# Tj_Monitor.net
KiCad netlist of a schematic drawn in Altium Designer
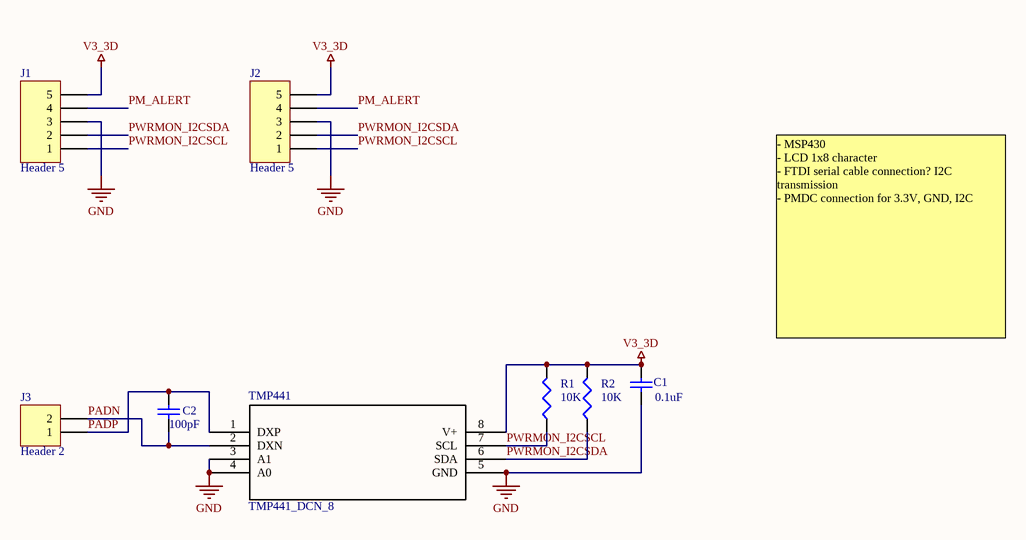
[diagram p0: Tj_Monitor.SchDoc]

(export (version "E")
  (design (tool "Eeschema 10.0.6"))
  (components
    (comp (ref "C1")
      (value "0.1uF")
      (footprint "0402")
      (description "Capacitor (Semiconductor SIM Model)")
      (fields (field (name "Comment") "Cap Semi") (field (name "PUBLISHER") "Altium Limited"))
      (libsource (lib "Miscellaneous Devices") (part "Cap Semi"))
    )
    (comp (ref "C2")
      (value "100pF")
      (footprint "0402")
      (description "Capacitor (Semiconductor SIM Model)")
      (fields (field (name "Comment") "Cap Semi") (field (name "PUBLISHER") "Altium Limited"))
      (libsource (lib "Miscellaneous Devices") (part "Cap Semi"))
    )
    (comp (ref "J1")
      (value "Header 5")
      (footprint "HDR1X5")
      (description "Header, 5-Pin")
      (fields (field (name "PUBLISHER") "Altium Limited"))
      (libsource (lib "Miscellaneous Connectors") (part "Header 5"))
    )
    (comp (ref "J2")
      (value "Header 5")
      (footprint "HDR1X5")
      (description "Header, 5-Pin")
      (fields (field (name "PUBLISHER") "Altium Limited"))
      (libsource (lib "Miscellaneous Connectors") (part "Header 5"))
    )
    (comp (ref "J3")
      (value "Header 2")
      (footprint "HDR1X2")
      (description "Header, 2-Pin")
      (fields (field (name "PUBLISHER") "Altium Limited"))
      (libsource (lib "Miscellaneous Connectors") (part "Header 2"))
    )
    (comp (ref "R1")
      (value "10K")
      (footprint "0402")
      (description "Resistor")
      (fields (field (name "Comment") "Res3") (field (name "PUBLISHER") "Altium Limited"))
      (libsource (lib "Miscellaneous Devices") (part "Res3"))
    )
    (comp (ref "R2")
      (value "10K")
      (footprint "0402")
      (description "Resistor")
      (fields (field (name "Comment") "Res3") (field (name "PUBLISHER") "Altium Limited"))
      (libsource (lib "Miscellaneous Devices") (part "Res3"))
    )
    (comp (ref "TMP441")
      (value "TMP441_DCN_8")
      (footprint "TMP441:DCN8-L")
      (description "Imported")
      (fields
        (field (name "MANUFACTURER_PART_NUMBER") "tmp441_dcn_8")
        (field (name "GENERIC_PART_NUMBER") "TMP441")
      )
      (libsource (lib "TMP441") (part "TMP441_DCN_8"))
    )
  )
  (nets
    (net (code "1") (name "/PADN") (class "Default")
      (node (ref "C2") (pin "1") (pinfunction "1_1") (pintype "passive"))
      (node (ref "J3") (pin "2") (pinfunction "2_2") (pintype "passive"))
      (node (ref "TMP441") (pin "2") (pinfunction "DXN_2") (pintype "passive"))
    )
    (net (code "2") (name "/PADP") (class "Default")
      (node (ref "C2") (pin "2") (pinfunction "2_2") (pintype "passive"))
      (node (ref "J3") (pin "1") (pinfunction "1_1") (pintype "passive"))
      (node (ref "TMP441") (pin "1") (pinfunction "DXP_1") (pintype "passive"))
    )
    (net (code "3") (name "/PM_ALERT") (class "Default")
      (node (ref "J1") (pin "4") (pinfunction "4_4") (pintype "passive"))
      (node (ref "J2") (pin "4") (pinfunction "4_4") (pintype "passive"))
    )
    (net (code "4") (name "/PWRMON_I2CSCL") (class "Default")
      (node (ref "J1") (pin "1") (pinfunction "1_1") (pintype "passive"))
      (node (ref "J2") (pin "1") (pinfunction "1_1") (pintype "passive"))
      (node (ref "R1") (pin "1") (pinfunction "1_1") (pintype "passive"))
      (node (ref "TMP441") (pin "7") (pinfunction "SCL_7") (pintype "passive"))
    )
    (net (code "5") (name "/PWRMON_I2CSDA") (class "Default")
      (node (ref "J1") (pin "2") (pinfunction "2_2") (pintype "passive"))
      (node (ref "J2") (pin "2") (pinfunction "2_2") (pintype "passive"))
      (node (ref "R2") (pin "1") (pinfunction "1_1") (pintype "passive"))
      (node (ref "TMP441") (pin "6") (pinfunction "SDA_6") (pintype "passive"))
    )
    (net (code "6") (name "GND") (class "Default")
      (node (ref "C1") (pin "1") (pinfunction "1_1") (pintype "passive"))
      (node (ref "J1") (pin "3") (pinfunction "3_3") (pintype "passive"))
      (node (ref "J2") (pin "3") (pinfunction "3_3") (pintype "passive"))
      (node (ref "TMP441") (pin "3") (pinfunction "A1_3") (pintype "passive"))
      (node (ref "TMP441") (pin "4") (pinfunction "A0_4") (pintype "passive"))
      (node (ref "TMP441") (pin "5") (pinfunction "GND_5") (pintype "power_in"))
    )
    (net (code "7") (name "V3_3D") (class "Default")
      (node (ref "C1") (pin "2") (pinfunction "2_2") (pintype "passive"))
      (node (ref "J1") (pin "5") (pinfunction "5_5") (pintype "passive"))
      (node (ref "J2") (pin "5") (pinfunction "5_5") (pintype "passive"))
      (node (ref "R1") (pin "2") (pinfunction "2_2") (pintype "passive"))
      (node (ref "R2") (pin "2") (pinfunction "2_2") (pintype "passive"))
      (node (ref "TMP441") (pin "8") (pinfunction "V+_8") (pintype "power_in"))
    )
  )
)
